# 03_-Heating_Element.net
KiCad netlist of a schematic drawn in Altium Designer
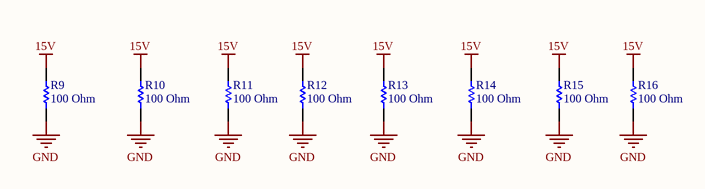
[diagram p0: [03]-Heating Element.SchDoc]

(export (version "E")
  (design (tool "Eeschema 10.0.6"))
  (components
    (comp (ref "R9")
      (value "100 Ohm")
      (footprint "RESC2010(5025)_N")
      (description "100 Ohms ±1% 2W Chip Resistor 2010 (5025 Metric) Thick Film")
      (fields
        (field (name "MPN") "3502100RFT")
        (field (name "MANUFACTURER") "TE Connectivity Passive Product")
      )
      (libsource (lib "Altium Content Vault") (part "RES"))
    )
    (comp (ref "R10")
      (value "100 Ohm")
      (footprint "RESC2010(5025)_N")
      (description "100 Ohms ±1% 2W Chip Resistor 2010 (5025 Metric) Thick Film")
      (fields
        (field (name "MPN") "3502100RFT")
        (field (name "MANUFACTURER") "TE Connectivity Passive Product")
      )
      (libsource (lib "Altium Content Vault") (part "RES"))
    )
    (comp (ref "R11")
      (value "100 Ohm")
      (footprint "RESC2010(5025)_N")
      (description "100 Ohms ±1% 2W Chip Resistor 2010 (5025 Metric) Thick Film")
      (fields
        (field (name "MPN") "3502100RFT")
        (field (name "MANUFACTURER") "TE Connectivity Passive Product")
      )
      (libsource (lib "Altium Content Vault") (part "RES"))
    )
    (comp (ref "R12")
      (value "100 Ohm")
      (footprint "RESC2010(5025)_N")
      (description "100 Ohms ±1% 2W Chip Resistor 2010 (5025 Metric) Thick Film")
      (fields
        (field (name "MPN") "3502100RFT")
        (field (name "MANUFACTURER") "TE Connectivity Passive Product")
      )
      (libsource (lib "Altium Content Vault") (part "RES"))
    )
    (comp (ref "R13")
      (value "100 Ohm")
      (footprint "RESC2010(5025)_N")
      (description "100 Ohms ±1% 2W Chip Resistor 2010 (5025 Metric) Thick Film")
      (fields
        (field (name "MPN") "3502100RFT")
        (field (name "MANUFACTURER") "TE Connectivity Passive Product")
      )
      (libsource (lib "Altium Content Vault") (part "RES"))
    )
    (comp (ref "R14")
      (value "100 Ohm")
      (footprint "RESC2010(5025)_N")
      (description "100 Ohms ±1% 2W Chip Resistor 2010 (5025 Metric) Thick Film")
      (fields
        (field (name "MPN") "3502100RFT")
        (field (name "MANUFACTURER") "TE Connectivity Passive Product")
      )
      (libsource (lib "Altium Content Vault") (part "RES"))
    )
    (comp (ref "R15")
      (value "100 Ohm")
      (footprint "RESC2010(5025)_N")
      (description "100 Ohms ±1% 2W Chip Resistor 2010 (5025 Metric) Thick Film")
      (fields
        (field (name "MPN") "3502100RFT")
        (field (name "MANUFACTURER") "TE Connectivity Passive Product")
      )
      (libsource (lib "Altium Content Vault") (part "RES"))
    )
    (comp (ref "R16")
      (value "100 Ohm")
      (footprint "RESC2010(5025)_N")
      (description "100 Ohms ±1% 2W Chip Resistor 2010 (5025 Metric) Thick Film")
      (fields
        (field (name "MPN") "3502100RFT")
        (field (name "MANUFACTURER") "TE Connectivity Passive Product")
      )
      (libsource (lib "Altium Content Vault") (part "RES"))
    )
  )
  (nets
    (net (code "1") (name "15V") (class "Default")
      (node (ref "R10") (pin "2") (pinfunction "2_2") (pintype "passive"))
      (node (ref "R11") (pin "2") (pinfunction "2_2") (pintype "passive"))
      (node (ref "R12") (pin "2") (pinfunction "2_2") (pintype "passive"))
      (node (ref "R13") (pin "2") (pinfunction "2_2") (pintype "passive"))
      (node (ref "R14") (pin "2") (pinfunction "2_2") (pintype "passive"))
      (node (ref "R15") (pin "2") (pinfunction "2_2") (pintype "passive"))
      (node (ref "R16") (pin "2") (pinfunction "2_2") (pintype "passive"))
      (node (ref "R9") (pin "2") (pinfunction "2_2") (pintype "passive"))
    )
    (net (code "2") (name "GND") (class "Default")
      (node (ref "R10") (pin "1") (pinfunction "1_1") (pintype "passive"))
      (node (ref "R11") (pin "1") (pinfunction "1_1") (pintype "passive"))
      (node (ref "R12") (pin "1") (pinfunction "1_1") (pintype "passive"))
      (node (ref "R13") (pin "1") (pinfunction "1_1") (pintype "passive"))
      (node (ref "R14") (pin "1") (pinfunction "1_1") (pintype "passive"))
      (node (ref "R15") (pin "1") (pinfunction "1_1") (pintype "passive"))
      (node (ref "R16") (pin "1") (pinfunction "1_1") (pintype "passive"))
      (node (ref "R9") (pin "1") (pinfunction "1_1") (pintype "passive"))
    )
  )
)
